# Endings_Controls.net
KiCad netlist of a schematic drawn in EAGLE
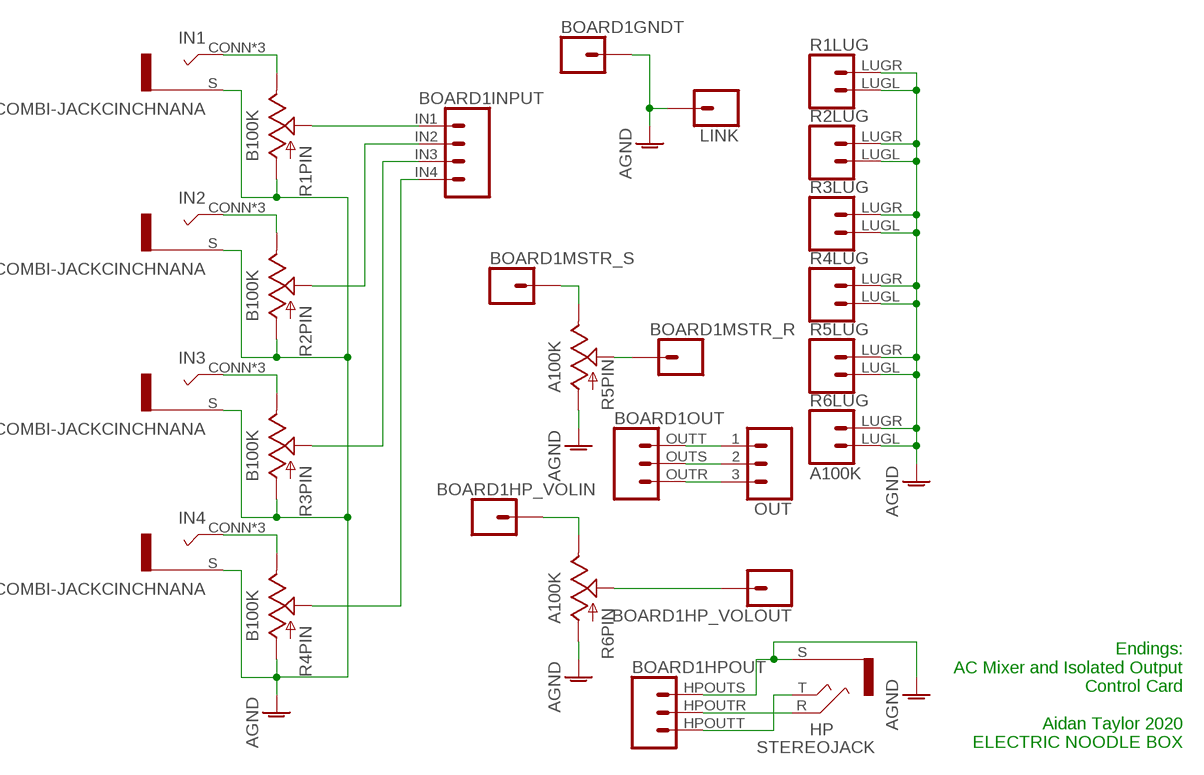
[diagram p0: schematic, sheet 1]

(export (version "E")
  (design (tool "Eeschema 10.0.6"))
  (components
    (comp (ref "BOARD1")
      (value "ENDINGS_LINK")
      (footprint "eagle-import:ENDINGS")
      (libsource (lib "eagle-import") (part "ENDINGS_LINK"))
    )
    (comp (ref "HP")
      (value "STEREOJACK")
      (footprint "eagle-import:STEREO_JACK_PANEL")
      (libsource (lib "eagle-import") (part "STEREOJACK"))
    )
    (comp (ref "IN1")
      (value "COMBI-JACKCINCHNANA")
      (footprint "eagle-import:NEWCOMBOJACK_PANEL")
      (libsource (lib "eagle-import") (part "COMBI-JACKCINCHNANA"))
    )
    (comp (ref "IN2")
      (value "COMBI-JACKCINCHNANA")
      (footprint "eagle-import:NEWCOMBOJACK_PANEL")
      (libsource (lib "eagle-import") (part "COMBI-JACKCINCHNANA"))
    )
    (comp (ref "IN3")
      (value "COMBI-JACKCINCHNANA")
      (footprint "eagle-import:NEWCOMBOJACK_PANEL")
      (libsource (lib "eagle-import") (part "COMBI-JACKCINCHNANA"))
    )
    (comp (ref "IN4")
      (value "COMBI-JACKCINCHNANA")
      (footprint "eagle-import:NEWCOMBOJACK_PANEL")
      (libsource (lib "eagle-import") (part "COMBI-JACKCINCHNANA"))
    )
    (comp (ref "LINK")
      (value "BANANA_PANEL")
      (footprint "eagle-import:CINCHNANA_PANEL")
      (libsource (lib "eagle-import") (part "BANANA_PANEL"))
    )
    (comp (ref "OUT")
      (value "3XWIREPAD")
      (footprint "eagle-import:1X03")
      (libsource (lib "eagle-import") (part "3XWIREPAD"))
    )
    (comp (ref "R1")
      (value "B100K")
      (footprint "eagle-import:ALPHA_RV09_9MMPOT")
      (libsource (lib "eagle-import") (part "POTENTIOMETER"))
    )
    (comp (ref "R2")
      (value "B100K")
      (footprint "eagle-import:ALPHA_RV09_9MMPOT")
      (libsource (lib "eagle-import") (part "POTENTIOMETER"))
    )
    (comp (ref "R3")
      (value "B100K")
      (footprint "eagle-import:ALPHA_RV09_9MMPOT")
      (libsource (lib "eagle-import") (part "POTENTIOMETER"))
    )
    (comp (ref "R4")
      (value "B100K")
      (footprint "eagle-import:ALPHA_RV09_9MMPOT")
      (libsource (lib "eagle-import") (part "POTENTIOMETER"))
    )
    (comp (ref "R5")
      (value "A100K")
      (footprint "eagle-import:ALPHA_RV09_9MMPOT")
      (libsource (lib "eagle-import") (part "POTENTIOMETER"))
    )
    (comp (ref "R6")
      (value "A100K")
      (footprint "eagle-import:ALPHA_RV09_9MMPOT")
      (libsource (lib "eagle-import") (part "POTENTIOMETER"))
    )
  )
  (nets
    (net (code "1") (name "AGND") (class "Default")
      (node (ref "BOARD1") (pin "GND1") (pinfunction "1_GND1") (pintype "passive"))
      (node (ref "BOARD1") (pin "GND2") (pinfunction "1_GND2") (pintype "passive"))
      (node (ref "BOARD1") (pin "GND3") (pinfunction "1_GND3") (pintype "passive"))
      (node (ref "BOARD1") (pin "GND4") (pinfunction "1_GND4") (pintype "passive"))
      (node (ref "BOARD1") (pin "HPOUTS") (pinfunction "3_HPOUTS") (pintype "passive"))
      (node (ref "HP") (pin "S") (pinfunction "S_S") (pintype "passive"))
      (node (ref "IN1") (pin "S") (pinfunction "S_S") (pintype "passive"))
      (node (ref "IN2") (pin "S") (pinfunction "S_S") (pintype "passive"))
      (node (ref "IN3") (pin "S") (pinfunction "S_S") (pintype "passive"))
      (node (ref "IN4") (pin "S") (pinfunction "S_S") (pintype "passive"))
      (node (ref "LINK") (pin "CONN") (pinfunction "1_CONN") (pintype "passive"))
      (node (ref "R1") (pin "C1") (pinfunction "A_C1") (pintype "passive"))
      (node (ref "R1") (pin "LUGL") (pinfunction "1_LUGL") (pintype "passive"))
      (node (ref "R1") (pin "LUGR") (pinfunction "2_LUGR") (pintype "passive"))
      (node (ref "R2") (pin "C1") (pinfunction "A_C1") (pintype "passive"))
      (node (ref "R2") (pin "LUGL") (pinfunction "1_LUGL") (pintype "passive"))
      (node (ref "R2") (pin "LUGR") (pinfunction "2_LUGR") (pintype "passive"))
      (node (ref "R3") (pin "C1") (pinfunction "A_C1") (pintype "passive"))
      (node (ref "R3") (pin "LUGL") (pinfunction "1_LUGL") (pintype "passive"))
      (node (ref "R3") (pin "LUGR") (pinfunction "2_LUGR") (pintype "passive"))
      (node (ref "R4") (pin "C1") (pinfunction "A_C1") (pintype "passive"))
      (node (ref "R4") (pin "LUGL") (pinfunction "1_LUGL") (pintype "passive"))
      (node (ref "R4") (pin "LUGR") (pinfunction "2_LUGR") (pintype "passive"))
      (node (ref "R5") (pin "C1") (pinfunction "A_C1") (pintype "passive"))
      (node (ref "R5") (pin "LUGL") (pinfunction "1_LUGL") (pintype "passive"))
      (node (ref "R5") (pin "LUGR") (pinfunction "2_LUGR") (pintype "passive"))
      (node (ref "R6") (pin "C1") (pinfunction "A_C1") (pintype "passive"))
      (node (ref "R6") (pin "LUGL") (pinfunction "1_LUGL") (pintype "passive"))
      (node (ref "R6") (pin "LUGR") (pinfunction "2_LUGR") (pintype "passive"))
    )
    (net (code "2") (name "Net-(BOARD1B-1)") (class "Default")
      (node (ref "BOARD1") (pin "HPOUTT") (pinfunction "1_HPOUTT") (pintype "passive"))
      (node (ref "HP") (pin "T") (pinfunction "T_T") (pintype "passive"))
    )
    (net (code "3") (name "Net-(BOARD1B-2)") (class "Default")
      (node (ref "BOARD1") (pin "HPOUTR") (pinfunction "2_HPOUTR") (pintype "passive"))
      (node (ref "HP") (pin "R") (pinfunction "R_R") (pintype "passive"))
    )
    (net (code "4") (name "Net-(BOARD1C-1)") (class "Default")
      (node (ref "BOARD1") (pin "HPVOLIN") (pinfunction "1_HPVOLIN") (pintype "passive"))
      (node (ref "R6") (pin "C3") (pinfunction "B_C3") (pintype "passive"))
    )
    (net (code "5") (name "Net-(BOARD1D-1)") (class "Default")
      (node (ref "BOARD1") (pin "HPVOLOUT") (pinfunction "1_HPVOLOUT") (pintype "passive"))
      (node (ref "R6") (pin "C2") (pinfunction "W_C2") (pintype "passive"))
    )
    (net (code "6") (name "Net-(BOARD1E-1)") (class "Default")
      (node (ref "BOARD1") (pin "IN1") (pinfunction "1_IN1") (pintype "passive"))
      (node (ref "R1") (pin "C2") (pinfunction "W_C2") (pintype "passive"))
    )
    (net (code "7") (name "Net-(BOARD1E-2)") (class "Default")
      (node (ref "BOARD1") (pin "IN2") (pinfunction "2_IN2") (pintype "passive"))
      (node (ref "R2") (pin "C2") (pinfunction "W_C2") (pintype "passive"))
    )
    (net (code "8") (name "Net-(BOARD1E-3)") (class "Default")
      (node (ref "BOARD1") (pin "IN3") (pinfunction "3_IN3") (pintype "passive"))
      (node (ref "R3") (pin "C2") (pinfunction "W_C2") (pintype "passive"))
    )
    (net (code "9") (name "Net-(BOARD1E-4)") (class "Default")
      (node (ref "BOARD1") (pin "IN4") (pinfunction "4_IN4") (pintype "passive"))
      (node (ref "R4") (pin "C2") (pinfunction "W_C2") (pintype "passive"))
    )
    (net (code "10") (name "Net-(BOARD1F-1)") (class "Default")
      (node (ref "BOARD1") (pin "MSTRVOLIN") (pinfunction "1_MSTRVOLIN") (pintype "passive"))
      (node (ref "R5") (pin "C2") (pinfunction "W_C2") (pintype "passive"))
    )
    (net (code "11") (name "Net-(BOARD1G-1)") (class "Default")
      (node (ref "BOARD1") (pin "MSTRVOLOUT") (pinfunction "1_MSTRVOLOUT") (pintype "passive"))
      (node (ref "R5") (pin "C3") (pinfunction "B_C3") (pintype "passive"))
    )
    (net (code "12") (name "Net-(BOARD1H-1)") (class "Default")
      (node (ref "BOARD1") (pin "OUTR") (pinfunction "1_OUTR") (pintype "passive"))
      (node (ref "OUT") (pin "3") (pinfunction "3_3") (pintype "passive"))
    )
    (net (code "13") (name "Net-(BOARD1H-2)") (class "Default")
      (node (ref "BOARD1") (pin "OUTS") (pinfunction "2_OUTS") (pintype "passive"))
      (node (ref "OUT") (pin "2") (pinfunction "2_2") (pintype "passive"))
    )
    (net (code "14") (name "Net-(BOARD1H-3)") (class "Default")
      (node (ref "BOARD1") (pin "OUTT") (pinfunction "3_OUTT") (pintype "passive"))
      (node (ref "OUT") (pin "1") (pinfunction "1_1") (pintype "passive"))
    )
    (net (code "15") (name "Net-(R1B-B)") (class "Default")
      (node (ref "IN1") (pin "CONN") (pinfunction "T_CONN") (pintype "passive"))
      (node (ref "IN1") (pin "T1") (pinfunction "T_T1") (pintype "passive"))
      (node (ref "IN1") (pin "T2") (pinfunction "T_T2") (pintype "passive"))
      (node (ref "R1") (pin "C3") (pinfunction "B_C3") (pintype "passive"))
    )
    (net (code "16") (name "Net-(R2B-B)") (class "Default")
      (node (ref "IN2") (pin "CONN") (pinfunction "T_CONN") (pintype "passive"))
      (node (ref "IN2") (pin "T1") (pinfunction "T_T1") (pintype "passive"))
      (node (ref "IN2") (pin "T2") (pinfunction "T_T2") (pintype "passive"))
      (node (ref "R2") (pin "C3") (pinfunction "B_C3") (pintype "passive"))
    )
    (net (code "17") (name "Net-(R3B-B)") (class "Default")
      (node (ref "IN3") (pin "CONN") (pinfunction "T_CONN") (pintype "passive"))
      (node (ref "IN3") (pin "T1") (pinfunction "T_T1") (pintype "passive"))
      (node (ref "IN3") (pin "T2") (pinfunction "T_T2") (pintype "passive"))
      (node (ref "R3") (pin "C3") (pinfunction "B_C3") (pintype "passive"))
    )
    (net (code "18") (name "Net-(R4B-B)") (class "Default")
      (node (ref "IN4") (pin "CONN") (pinfunction "T_CONN") (pintype "passive"))
      (node (ref "IN4") (pin "T1") (pinfunction "T_T1") (pintype "passive"))
      (node (ref "IN4") (pin "T2") (pinfunction "T_T2") (pintype "passive"))
      (node (ref "R4") (pin "C3") (pinfunction "B_C3") (pintype "passive"))
    )
  )
)
